# quadstick1.net
KiCad netlist of a schematic drawn in EAGLE
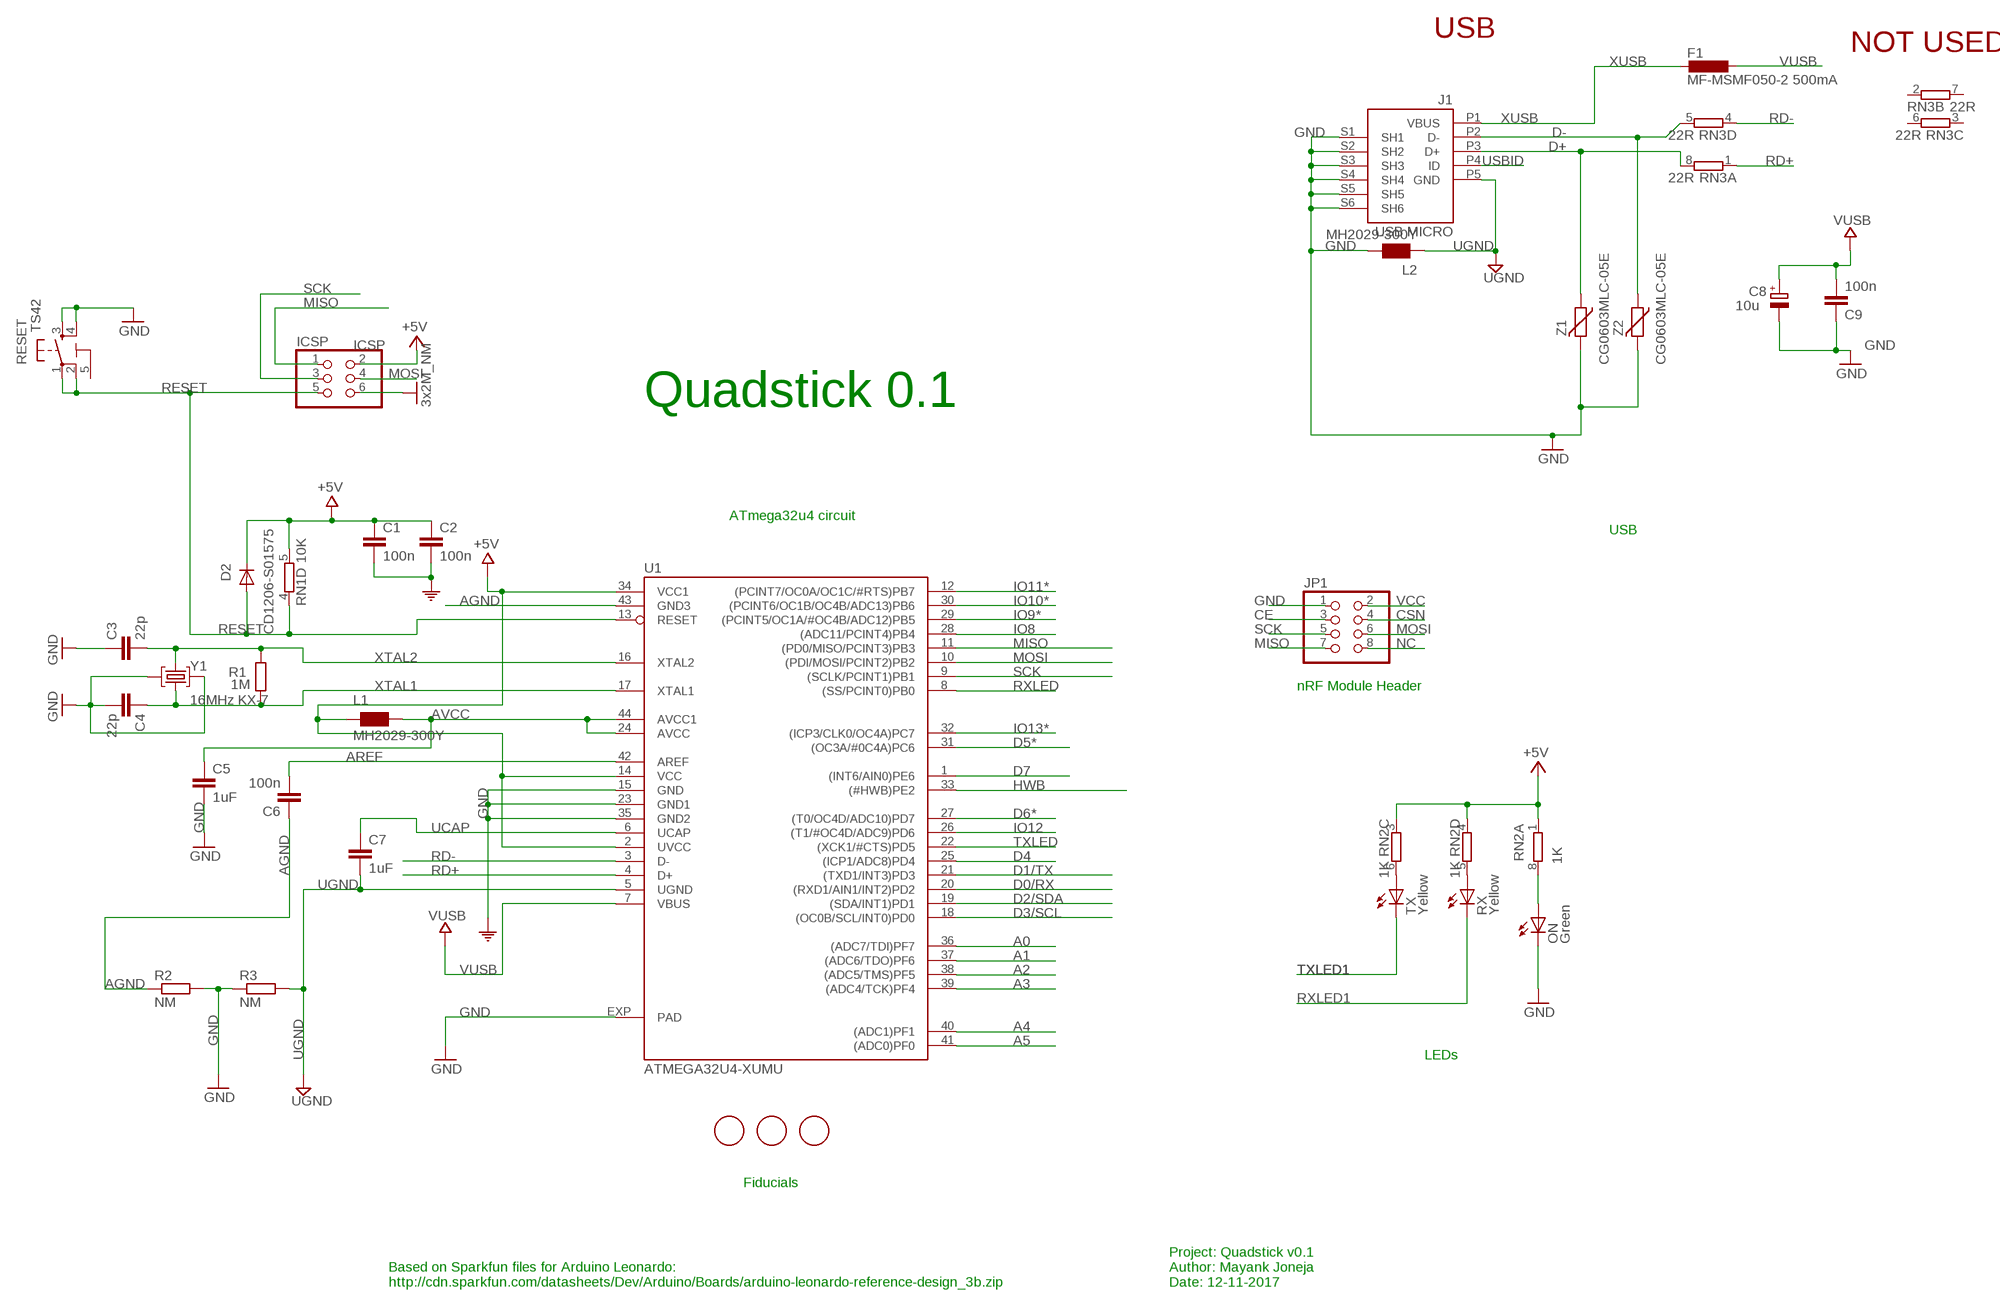
[diagram p0: schematic, sheet 1]

(export (version "E")
  (design (tool "Eeschema 10.0.6"))
  (components
    (comp (ref "C1")
      (value "100n")
      (footprint "eagle-import:C0603-ROUND")
      (libsource (lib "eagle-import") (part "C-EUC0603"))
    )
    (comp (ref "C2")
      (value "100n")
      (footprint "eagle-import:C0603-ROUND")
      (libsource (lib "eagle-import") (part "C-EUC0603"))
    )
    (comp (ref "C3")
      (value "22p")
      (footprint "eagle-import:C0603-ROUND")
      (libsource (lib "eagle-import") (part "C-EUC0603"))
    )
    (comp (ref "C4")
      (value "22p")
      (footprint "eagle-import:C0603-ROUND")
      (libsource (lib "eagle-import") (part "C-EUC0603"))
    )
    (comp (ref "C5")
      (value "1uF")
      (footprint "eagle-import:C0603-ROUND")
      (libsource (lib "eagle-import") (part "C-EUC0603"))
    )
    (comp (ref "C6")
      (value "100n")
      (footprint "eagle-import:C0603-ROUND")
      (libsource (lib "eagle-import") (part "C-EUC0603"))
    )
    (comp (ref "C7")
      (value "1uF")
      (footprint "eagle-import:C0603-ROUND")
      (libsource (lib "eagle-import") (part "C-EUC0603"))
    )
    (comp (ref "C8")
      (value "10u")
      (footprint "eagle-import:SMC_B")
      (libsource (lib "eagle-import") (part "CPOL-EUSMCB"))
    )
    (comp (ref "C9")
      (value "100n")
      (footprint "eagle-import:C0603-ROUND")
      (libsource (lib "eagle-import") (part "C-EUC0603"))
    )
    (comp (ref "D2")
      (value "CD1206-S01575")
      (footprint "eagle-import:MINIMELF")
      (libsource (lib "eagle-import") (part "DIODE-MINIMELF"))
    )
    (comp (ref "F1")
      (value "MF-MSMF050-2 500mA")
      (footprint "eagle-import:L1812")
      (libsource (lib "eagle-import") (part "L-EUL1812"))
    )
    (comp (ref "FID1")
      (value "FIDUCIALMOUNT")
      (footprint "eagle-import:FIDUCIA-MOUNT")
      (libsource (lib "eagle-import") (part "FIDUCIALMOUNT"))
    )
    (comp (ref "FID2")
      (value "FIDUCIALMOUNT")
      (footprint "eagle-import:FIDUCIA-MOUNT")
      (libsource (lib "eagle-import") (part "FIDUCIALMOUNT"))
    )
    (comp (ref "FID3")
      (value "FIDUCIALMOUNT")
      (footprint "eagle-import:FIDUCIA-MOUNT")
      (libsource (lib "eagle-import") (part "FIDUCIALMOUNT"))
    )
    (comp (ref "ICSP")
      (value "ICSP")
      (footprint "eagle-import:2X03")
      (libsource (lib "eagle-import") (part "PINHD-2X3"))
    )
    (comp (ref "J1")
      (value "USB MICRO")
      (footprint "eagle-import:CON2_USB_MICRO_B_AT")
      (libsource (lib "eagle-import") (part "MYCON2_USB-MINI-B"))
    )
    (comp (ref "JP1")
      (value "PINHD-2X4")
      (footprint "eagle-import:2X04")
      (libsource (lib "eagle-import") (part "PINHD-2X4"))
    )
    (comp (ref "L1")
      (value "MH2029-300Y")
      (footprint "eagle-import:0805")
      (libsource (lib "eagle-import") (part "WE-CBF_0805"))
    )
    (comp (ref "L2")
      (value "MH2029-300Y")
      (footprint "eagle-import:0805")
      (libsource (lib "eagle-import") (part "WE-CBF_0805"))
    )
    (comp (ref "ON")
      (value "Green")
      (footprint "eagle-import:CHIPLED_0805")
      (libsource (lib "eagle-import") (part "LEDCHIPLED_0805"))
    )
    (comp (ref "R1")
      (value "1M")
      (footprint "eagle-import:R0603-ROUND")
      (libsource (lib "eagle-import") (part "R-EU_R0603"))
    )
    (comp (ref "R2")
      (value "NM")
      (footprint "eagle-import:R0402")
      (libsource (lib "eagle-import") (part "R-EU_R0402"))
    )
    (comp (ref "R3")
      (value "NM")
      (footprint "eagle-import:R0402")
      (libsource (lib "eagle-import") (part "R-EU_R0402"))
    )
    (comp (ref "RESET")
      (value "TS42")
      (footprint "eagle-import:TS42")
      (libsource (lib "eagle-import") (part "TS42"))
    )
    (comp (ref "RN1")
      (value "10K")
      (footprint "eagle-import:CAY16")
      (libsource (lib "eagle-import") (part "4R-NCAY16"))
    )
    (comp (ref "RN2")
      (value "1K")
      (footprint "eagle-import:CAY16")
      (libsource (lib "eagle-import") (part "4R-NCAY16"))
    )
    (comp (ref "RN3")
      (value "22R")
      (footprint "eagle-import:CAY16")
      (libsource (lib "eagle-import") (part "4R-NCAY16"))
    )
    (comp (ref "RX")
      (value "Yellow")
      (footprint "eagle-import:CHIPLED_0805")
      (libsource (lib "eagle-import") (part "LEDCHIPLED_0805"))
    )
    (comp (ref "TX")
      (value "Yellow")
      (footprint "eagle-import:CHIPLED_0805")
      (libsource (lib "eagle-import") (part "LEDCHIPLED_0805"))
    )
    (comp (ref "U1")
      (value "ATMEGA32U4-XUMU")
      (footprint "eagle-import:QFN44ML7X7")
      (libsource (lib "eagle-import") (part "ATMEGA32U4-XUMU"))
    )
    (comp (ref "Y1")
      (value "16MHz KX-7")
      (footprint "eagle-import:CRYSTAL-3.2-2.5")
      (libsource (lib "eagle-import") (part "CRYSTAL-3.2-2.5"))
    )
    (comp (ref "Z1")
      (value "CG0603MLC-05E")
      (footprint "eagle-import:CT_CN0603")
      (libsource (lib "eagle-import") (part "VARISTORCN0603"))
    )
    (comp (ref "Z2")
      (value "CG0603MLC-05E")
      (footprint "eagle-import:CT_CN0603")
      (libsource (lib "eagle-import") (part "VARISTORCN0603"))
    )
  )
  (nets
    (net (code "1") (name "+5V") (class "Default")
      (node (ref "C1") (pin "1") (pinfunction "1_1") (pintype "passive"))
      (node (ref "C2") (pin "1") (pinfunction "1_1") (pintype "passive"))
      (node (ref "D2") (pin "C") (pinfunction "C_C") (pintype "passive"))
      (node (ref "ICSP") (pin "2") (pinfunction "2_2") (pintype "passive"))
      (node (ref "L1") (pin "1") (pinfunction "1_1") (pintype "passive"))
      (node (ref "RN1") (pin "5") (pinfunction "2_5") (pintype "passive"))
      (node (ref "RN2") (pin "1") (pinfunction "1_1") (pintype "passive"))
      (node (ref "RN2") (pin "3") (pinfunction "1_3") (pintype "passive"))
      (node (ref "RN2") (pin "4") (pinfunction "1_4") (pintype "passive"))
      (node (ref "U1") (pin "14") (pinfunction "VCC_14") (pintype "power_in"))
      (node (ref "U1") (pin "2") (pinfunction "UVCC_2") (pintype "power_in"))
      (node (ref "U1") (pin "34") (pinfunction "VCC1_34") (pintype "power_in"))
    )
    (net (code "2") (name "/5-GND") (class "Default")
      (node (ref "RESET") (pin "5") (pinfunction "5-GND_5") (pintype "power_in"))
    )
    (net (code "3") (name "/A0") (class "Default")
      (node (ref "U1") (pin "36") (pinfunction "(ADC7/TDI)PF7_36") (pintype "bidirectional"))
    )
    (net (code "4") (name "/A1") (class "Default")
      (node (ref "U1") (pin "37") (pinfunction "(ADC6/TDO)PF6_37") (pintype "bidirectional"))
    )
    (net (code "5") (name "/A2") (class "Default")
      (node (ref "U1") (pin "38") (pinfunction "(ADC5/TMS)PF5_38") (pintype "bidirectional"))
    )
    (net (code "6") (name "/A3") (class "Default")
      (node (ref "U1") (pin "39") (pinfunction "(ADC4/TCK)PF4_39") (pintype "bidirectional"))
    )
    (net (code "7") (name "/A4") (class "Default")
      (node (ref "U1") (pin "40") (pinfunction "(ADC1)PF1_40") (pintype "bidirectional"))
    )
    (net (code "8") (name "/A5") (class "Default")
      (node (ref "U1") (pin "41") (pinfunction "(ADC0)PF0_41") (pintype "bidirectional"))
    )
    (net (code "9") (name "/AGND") (class "Default")
      (node (ref "C6") (pin "1") (pinfunction "1_1") (pintype "passive"))
      (node (ref "R2") (pin "1") (pinfunction "1_1") (pintype "passive"))
      (node (ref "U1") (pin "43") (pinfunction "GND3_43") (pintype "power_in"))
    )
    (net (code "10") (name "/AREF") (class "Default")
      (node (ref "C6") (pin "2") (pinfunction "2_2") (pintype "passive"))
      (node (ref "U1") (pin "42") (pinfunction "AREF_42") (pintype "power_in"))
    )
    (net (code "11") (name "/AVCC") (class "Default")
      (node (ref "C5") (pin "1") (pinfunction "1_1") (pintype "passive"))
      (node (ref "L1") (pin "2") (pinfunction "2_2") (pintype "passive"))
      (node (ref "U1") (pin "24") (pinfunction "AVCC_24") (pintype "power_in"))
      (node (ref "U1") (pin "44") (pinfunction "AVCC1_44") (pintype "power_in"))
    )
    (net (code "12") (name "/CE") (class "Default")
      (node (ref "JP1") (pin "3") (pinfunction "3_3") (pintype "passive"))
    )
    (net (code "13") (name "/CSN") (class "Default")
      (node (ref "JP1") (pin "4") (pinfunction "4_4") (pintype "passive"))
    )
    (net (code "14") (name "/D+") (class "Default")
      (node (ref "J1") (pin "P3") (pinfunction "D+_P3") (pintype "bidirectional"))
      (node (ref "RN3") (pin "8") (pinfunction "2_8") (pintype "passive"))
      (node (ref "Z1") (pin "1") (pinfunction "1_1") (pintype "passive"))
    )
    (net (code "15") (name "/D-") (class "Default")
      (node (ref "J1") (pin "P2") (pinfunction "D-_P2") (pintype "bidirectional"))
      (node (ref "RN3") (pin "5") (pinfunction "2_5") (pintype "passive"))
      (node (ref "Z2") (pin "1") (pinfunction "1_1") (pintype "passive"))
    )
    (net (code "16") (name "/D0{slash}RX") (class "Default")
      (node (ref "U1") (pin "20") (pinfunction "(RXD1/AIN1/INT2)PD2_20") (pintype "bidirectional"))
    )
    (net (code "17") (name "/D1{slash}TX") (class "Default")
      (node (ref "U1") (pin "21") (pinfunction "(TXD1/INT3)PD3_21") (pintype "bidirectional"))
    )
    (net (code "18") (name "/D2{slash}SDA") (class "Default")
      (node (ref "U1") (pin "19") (pinfunction "(SDA/INT1)PD1_19") (pintype "bidirectional"))
    )
    (net (code "19") (name "/D3{slash}SCL") (class "Default")
      (node (ref "U1") (pin "18") (pinfunction "(OC0B/SCL/INT0)PD0_18") (pintype "bidirectional"))
    )
    (net (code "20") (name "/D4") (class "Default")
      (node (ref "U1") (pin "25") (pinfunction "(ICP1/ADC8)PD4_25") (pintype "bidirectional"))
    )
    (net (code "21") (name "/D5*") (class "Default")
      (node (ref "U1") (pin "31") (pinfunction "(OC3A/#0C4A)PC6_31") (pintype "bidirectional"))
    )
    (net (code "22") (name "/D6*") (class "Default")
      (node (ref "U1") (pin "27") (pinfunction "(T0/OC4D/ADC10)PD7_27") (pintype "bidirectional"))
    )
    (net (code "23") (name "/D7") (class "Default")
      (node (ref "U1") (pin "1") (pinfunction "(INT6/AIN0)PE6_1") (pintype "bidirectional"))
    )
    (net (code "24") (name "/HWB") (class "Default")
      (node (ref "U1") (pin "33") (pinfunction "(#HWB)PE2_33") (pintype "bidirectional"))
    )
    (net (code "25") (name "/IO8") (class "Default")
      (node (ref "U1") (pin "28") (pinfunction "(ADC11/PCINT4)PB4_28") (pintype "bidirectional"))
    )
    (net (code "26") (name "/IO9*") (class "Default")
      (node (ref "U1") (pin "29") (pinfunction "(PCINT5/OC1A/#OC4B/ADC12)PB5_29") (pintype "bidirectional"))
    )
    (net (code "27") (name "/IO10*") (class "Default")
      (node (ref "U1") (pin "30") (pinfunction "(PCINT6/OC1B/OC4B/ADC13)PB6_30") (pintype "bidirectional"))
    )
    (net (code "28") (name "/IO11*") (class "Default")
      (node (ref "U1") (pin "12") (pinfunction "(PCINT7/OC0A/OC1C/#RTS)PB7_12") (pintype "bidirectional"))
    )
    (net (code "29") (name "/IO12") (class "Default")
      (node (ref "U1") (pin "26") (pinfunction "(T1/#OC4D/ADC9)PD6_26") (pintype "bidirectional"))
    )
    (net (code "30") (name "/IO13*") (class "Default")
      (node (ref "U1") (pin "32") (pinfunction "(ICP3/CLK0/OC4A)PC7_32") (pintype "bidirectional"))
    )
    (net (code "31") (name "/MISO") (class "Default")
      (node (ref "ICSP") (pin "1") (pinfunction "1_1") (pintype "passive"))
      (node (ref "JP1") (pin "7") (pinfunction "7_7") (pintype "passive"))
      (node (ref "U1") (pin "11") (pinfunction "(PD0/MISO/PCINT3)PB3_11") (pintype "bidirectional"))
    )
    (net (code "32") (name "/MOSI") (class "Default")
      (node (ref "ICSP") (pin "4") (pinfunction "4_4") (pintype "passive"))
      (node (ref "JP1") (pin "6") (pinfunction "6_6") (pintype "passive"))
      (node (ref "U1") (pin "10") (pinfunction "(PDI/MOSI/PCINT2)PB2_10") (pintype "bidirectional"))
    )
    (net (code "33") (name "/NC") (class "Default")
      (node (ref "JP1") (pin "8") (pinfunction "8_8") (pintype "passive"))
    )
    (net (code "34") (name "/RD+") (class "Default")
      (node (ref "RN3") (pin "1") (pinfunction "1_1") (pintype "passive"))
      (node (ref "U1") (pin "4") (pinfunction "D+_4") (pintype "bidirectional"))
    )
    (net (code "35") (name "/RD-") (class "Default")
      (node (ref "RN3") (pin "4") (pinfunction "1_4") (pintype "passive"))
      (node (ref "U1") (pin "3") (pinfunction "D-_3") (pintype "bidirectional"))
    )
    (net (code "36") (name "/RESET") (class "Default")
      (node (ref "D2") (pin "A") (pinfunction "A_A") (pintype "passive"))
      (node (ref "ICSP") (pin "5") (pinfunction "5_5") (pintype "passive"))
      (node (ref "RESET") (pin "1") (pinfunction "1_1") (pintype "passive"))
      (node (ref "RESET") (pin "2") (pinfunction "2_2") (pintype "passive"))
      (node (ref "RN1") (pin "4") (pinfunction "1_4") (pintype "passive"))
      (node (ref "U1") (pin "13") (pinfunction "RESET_13") (pintype "input"))
    )
    (net (code "37") (name "/RXLED") (class "Default")
      (node (ref "U1") (pin "8") (pinfunction "(SS/PCINT0)PB0_8") (pintype "bidirectional"))
    )
    (net (code "38") (name "/RXLED1") (class "Default")
      (node (ref "RX") (pin "C") (pinfunction "C_C") (pintype "passive"))
    )
    (net (code "39") (name "/SCK") (class "Default")
      (node (ref "ICSP") (pin "3") (pinfunction "3_3") (pintype "passive"))
      (node (ref "JP1") (pin "5") (pinfunction "5_5") (pintype "passive"))
      (node (ref "U1") (pin "9") (pinfunction "(SCLK/PCINT1)PB1_9") (pintype "bidirectional"))
    )
    (net (code "40") (name "/TXLED") (class "Default")
      (node (ref "U1") (pin "22") (pinfunction "(XCK1/#CTS)PD5_22") (pintype "bidirectional"))
    )
    (net (code "41") (name "/TXLED1") (class "Default")
      (node (ref "TX") (pin "C") (pinfunction "C_C") (pintype "passive"))
    )
    (net (code "42") (name "/UCAP") (class "Default")
      (node (ref "C7") (pin "1") (pinfunction "1_1") (pintype "passive"))
      (node (ref "U1") (pin "6") (pinfunction "UCAP_6") (pintype "passive"))
    )
    (net (code "43") (name "/USBID") (class "Default")
      (node (ref "J1") (pin "P4") (pinfunction "ID_P4") (pintype "bidirectional"))
    )
    (net (code "44") (name "/VCC") (class "Default")
      (node (ref "JP1") (pin "2") (pinfunction "2_2") (pintype "passive"))
    )
    (net (code "45") (name "/XTAL1") (class "Default")
      (node (ref "C4") (pin "1") (pinfunction "1_1") (pintype "passive"))
      (node (ref "R1") (pin "1") (pinfunction "1_1") (pintype "passive"))
      (node (ref "U1") (pin "17") (pinfunction "XTAL1_17") (pintype "bidirectional"))
      (node (ref "Y1") (pin "1") (pinfunction "C1_1") (pintype "passive"))
    )
    (net (code "46") (name "/XTAL2") (class "Default")
      (node (ref "C3") (pin "2") (pinfunction "2_2") (pintype "passive"))
      (node (ref "R1") (pin "2") (pinfunction "2_2") (pintype "passive"))
      (node (ref "U1") (pin "16") (pinfunction "XTAL2_16") (pintype "bidirectional"))
      (node (ref "Y1") (pin "3") (pinfunction "C2_3") (pintype "passive"))
    )
    (net (code "47") (name "/XUSB") (class "Default")
      (node (ref "F1") (pin "2") (pinfunction "2_2") (pintype "passive"))
      (node (ref "J1") (pin "P1") (pinfunction "VBUS_P1") (pintype "power_in"))
    )
    (net (code "48") (name "3x2M_NM") (class "Default")
      (node (ref "C1") (pin "2") (pinfunction "2_2") (pintype "passive"))
      (node (ref "C2") (pin "2") (pinfunction "2_2") (pintype "passive"))
      (node (ref "C3") (pin "1") (pinfunction "1_1") (pintype "passive"))
      (node (ref "C4") (pin "2") (pinfunction "2_2") (pintype "passive"))
      (node (ref "C5") (pin "2") (pinfunction "2_2") (pintype "passive"))
      (node (ref "C8") (pin "-") (pinfunction "-_-") (pintype "passive"))
      (node (ref "C9") (pin "1") (pinfunction "1_1") (pintype "passive"))
      (node (ref "ICSP") (pin "6") (pinfunction "6_6") (pintype "passive"))
      (node (ref "J1") (pin "S1") (pinfunction "SH1_S1") (pintype "passive"))
      (node (ref "J1") (pin "S2") (pinfunction "SH2_S2") (pintype "passive"))
      (node (ref "J1") (pin "S3") (pinfunction "SH3_S3") (pintype "passive"))
      (node (ref "J1") (pin "S4") (pinfunction "SH4_S4") (pintype "passive"))
      (node (ref "J1") (pin "S5") (pinfunction "SH5_S5") (pintype "passive"))
      (node (ref "J1") (pin "S6") (pinfunction "SH6_S6") (pintype "passive"))
      (node (ref "JP1") (pin "1") (pinfunction "1_1") (pintype "passive"))
      (node (ref "L2") (pin "2") (pinfunction "2_2") (pintype "passive"))
      (node (ref "ON") (pin "C") (pinfunction "C_C") (pintype "passive"))
      (node (ref "R2") (pin "2") (pinfunction "2_2") (pintype "passive"))
      (node (ref "R3") (pin "1") (pinfunction "1_1") (pintype "passive"))
      (node (ref "RESET") (pin "3") (pinfunction "3_3") (pintype "passive"))
      (node (ref "RESET") (pin "4") (pinfunction "4_4") (pintype "passive"))
      (node (ref "U1") (pin "15") (pinfunction "GND_15") (pintype "power_in"))
      (node (ref "U1") (pin "23") (pinfunction "GND1_23") (pintype "power_in"))
      (node (ref "U1") (pin "35") (pinfunction "GND2_35") (pintype "power_in"))
      (node (ref "U1") (pin "EXP") (pinfunction "PAD_EXP") (pintype "power_in"))
      (node (ref "Y1") (pin "2") (pinfunction "GND_2") (pintype "passive"))
      (node (ref "Y1") (pin "4") (pinfunction "GND_4") (pintype "passive"))
      (node (ref "Z1") (pin "2") (pinfunction "2_2") (pintype "passive"))
      (node (ref "Z2") (pin "2") (pinfunction "2_2") (pintype "passive"))
    )
    (net (code "49") (name "Net-(RN2A-2)") (class "Default")
      (node (ref "ON") (pin "A") (pinfunction "A_A") (pintype "passive"))
      (node (ref "RN2") (pin "8") (pinfunction "2_8") (pintype "passive"))
    )
    (net (code "50") (name "Net-(RN2C-2)") (class "Default")
      (node (ref "RN2") (pin "6") (pinfunction "2_6") (pintype "passive"))
      (node (ref "TX") (pin "A") (pinfunction "A_A") (pintype "passive"))
    )
    (net (code "51") (name "Net-(RN2D-2)") (class "Default")
      (node (ref "RN2") (pin "5") (pinfunction "2_5") (pintype "passive"))
      (node (ref "RX") (pin "A") (pinfunction "A_A") (pintype "passive"))
    )
    (net (code "52") (name "UGND") (class "Default")
      (node (ref "C7") (pin "2") (pinfunction "2_2") (pintype "passive"))
      (node (ref "J1") (pin "P5") (pinfunction "GND_P5") (pintype "passive"))
      (node (ref "L2") (pin "1") (pinfunction "1_1") (pintype "passive"))
      (node (ref "R3") (pin "2") (pinfunction "2_2") (pintype "passive"))
      (node (ref "U1") (pin "5") (pinfunction "UGND_5") (pintype "power_in"))
    )
    (net (code "53") (name "VUSB") (class "Default")
      (node (ref "C8") (pin "+") (pinfunction "+_+") (pintype "passive"))
      (node (ref "C9") (pin "2") (pinfunction "2_2") (pintype "passive"))
      (node (ref "F1") (pin "1") (pinfunction "1_1") (pintype "passive"))
      (node (ref "U1") (pin "7") (pinfunction "VBUS_7") (pintype "input"))
    )
    (net (code "54") (name "unconnected-(RN3B-1-Pad2)") (class "Default")
      (node (ref "RN3") (pin "2") (pinfunction "1_2") (pintype "passive"))
    )
    (net (code "55") (name "unconnected-(RN3B-2-Pad7)") (class "Default")
      (node (ref "RN3") (pin "7") (pinfunction "2_7") (pintype "passive"))
    )
    (net (code "56") (name "unconnected-(RN3C-1-Pad3)") (class "Default")
      (node (ref "RN3") (pin "3") (pinfunction "1_3") (pintype "passive"))
    )
    (net (code "57") (name "unconnected-(RN3C-2-Pad6)") (class "Default")
      (node (ref "RN3") (pin "6") (pinfunction "2_6") (pintype "passive"))
    )
  )
)
